# uTracker.net
KiCad netlist of a schematic drawn in EAGLE
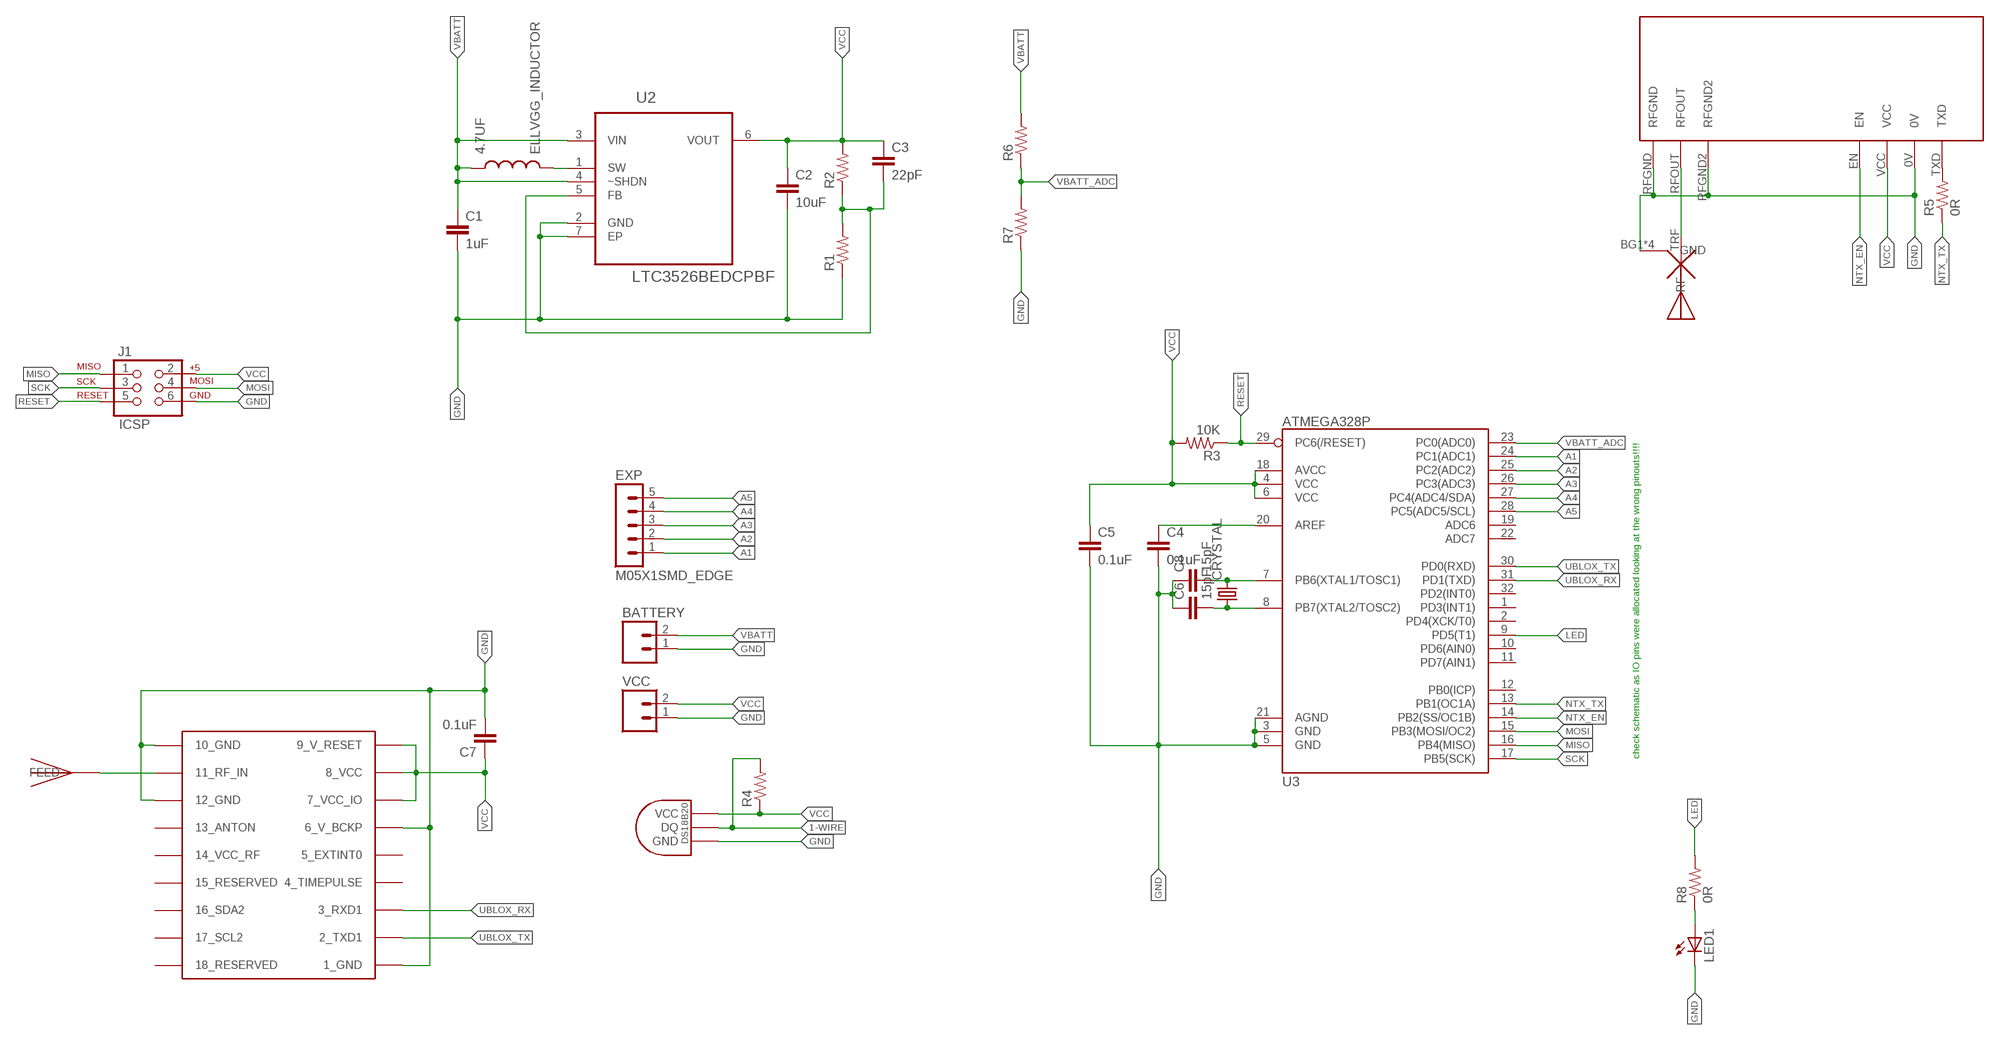
[diagram p0: schematic, sheet 1]

(export (version "E")
  (design (tool "Eeschema 10.0.6"))
  (components
    (comp (ref "4.7UF")
      (value "ELLVGG_INDUCTOR")
      (footprint "eagle-import:ELLVGG_INDUCTOR")
      (libsource (lib "eagle-import") (part "ELLVGG_INDUCTOR"))
    )
    (comp (ref "BATTERY")
      (value "M02PTH")
      (footprint "eagle-import:1X02")
      (libsource (lib "eagle-import") (part "M02PTH"))
    )
    (comp (ref "C1")
      (value "1uF")
      (footprint "eagle-import:0805")
      (libsource (lib "eagle-import") (part "CAP0805"))
    )
    (comp (ref "C2")
      (value "10uF")
      (footprint "eagle-import:0805")
      (libsource (lib "eagle-import") (part "CAP0805"))
    )
    (comp (ref "C3")
      (value "22pF")
      (footprint "eagle-import:0805")
      (libsource (lib "eagle-import") (part "CAP0805"))
    )
    (comp (ref "C4")
      (value "0.1uF")
      (footprint "eagle-import:0805")
      (libsource (lib "eagle-import") (part "CAP0805"))
    )
    (comp (ref "C5")
      (value "0.1uF")
      (footprint "eagle-import:0805")
      (libsource (lib "eagle-import") (part "CAP0805"))
    )
    (comp (ref "C6")
      (value "15pF")
      (footprint "eagle-import:0805")
      (libsource (lib "eagle-import") (part "CAP0805"))
    )
    (comp (ref "C7")
      (value "0.1uF")
      (footprint "eagle-import:0805")
      (libsource (lib "eagle-import") (part "CAP0805"))
    )
    (comp (ref "C8")
      (value "15pF")
      (footprint "eagle-import:0805")
      (libsource (lib "eagle-import") (part "CAP0805"))
    )
    (comp (ref "CRYSTAL")
      (value "ABRACON_ABM3_CRYSTALABM03_HC49")
      (footprint "eagle-import:ABM03_HC49")
      (libsource (lib "eagle-import") (part "ABRACON_ABM3_CRYSTALABM03_HC49"))
    )
    (comp (ref "EXP")
      (value "M05X1SMD_EDGE")
      (footprint "eagle-import:M05_SMD_EDGE")
      (libsource (lib "eagle-import") (part "M05X1SMD_EDGE"))
    )
    (comp (ref "J1")
      (value "ICSP")
      (footprint "eagle-import:ICSP_SMD_EDGE")
      (libsource (lib "eagle-import") (part "AVR_SPI_PRG_6SMD_EDGE"))
    )
    (comp (ref "LED1")
      (value "LED1206")
      (footprint "eagle-import:LED-1206")
      (libsource (lib "eagle-import") (part "LED1206"))
    )
    (comp (ref "R1")
      (value "RESISTOR0805-RES")
      (footprint "eagle-import:0805")
      (libsource (lib "eagle-import") (part "RESISTOR0805-RES"))
    )
    (comp (ref "R2")
      (value "RESISTOR0805-RES")
      (footprint "eagle-import:0805")
      (libsource (lib "eagle-import") (part "RESISTOR0805-RES"))
    )
    (comp (ref "R3")
      (value "10K")
      (footprint "eagle-import:0805")
      (libsource (lib "eagle-import") (part "RESISTOR0805-RES"))
    )
    (comp (ref "R4")
      (value "RESISTOR0805-RES")
      (footprint "eagle-import:0805")
      (libsource (lib "eagle-import") (part "RESISTOR0805-RES"))
    )
    (comp (ref "R5")
      (value "0R")
      (footprint "eagle-import:0805")
      (libsource (lib "eagle-import") (part "RESISTOR0805-RES"))
    )
    (comp (ref "R6")
      (value "RESISTOR0805-RES")
      (footprint "eagle-import:0805")
      (libsource (lib "eagle-import") (part "RESISTOR0805-RES"))
    )
    (comp (ref "R7")
      (value "RESISTOR0805-RES")
      (footprint "eagle-import:0805")
      (libsource (lib "eagle-import") (part "RESISTOR0805-RES"))
    )
    (comp (ref "R8")
      (value "0R")
      (footprint "eagle-import:0805")
      (libsource (lib "eagle-import") (part "RESISTOR0805-RES"))
    )
    (comp (ref "U$1")
      (value "ANTENNA")
      (footprint "eagle-import:ANTCONN_GNDPL")
      (libsource (lib "eagle-import") (part "ANTENNA"))
    )
    (comp (ref "U$2")
      (value "JTI_ANTENNA-1575AT43A40")
      (footprint "eagle-import:JTI_ANTENNA-1575AT43A40")
      (libsource (lib "eagle-import") (part "JTI_ANTENNA-1575AT43A40"))
    )
    (comp (ref "U$3")
      (value "NTX2")
      (footprint "eagle-import:NTX2")
      (libsource (lib "eagle-import") (part "NTX2"))
    )
    (comp (ref "U$4")
      (value "DS1820SOIC")
      (footprint "eagle-import:DS18B20_SOIC")
      (libsource (lib "eagle-import") (part "DS1820SOIC"))
    )
    (comp (ref "U2")
      (value "LTC3526BEDCPBF")
      (footprint "eagle-import:DFN200X200X80-7N")
      (fields (field (name "MPN") "LTC3526BEDC#PBF"))
      (libsource (lib "eagle-import") (part "LTC3526BEDCPBF"))
    )
    (comp (ref "U3")
      (value "ATMEGA328P")
      (footprint "eagle-import:TQFP32-08")
      (libsource (lib "eagle-import") (part "ATMEGA328_SMT"))
    )
    (comp (ref "UBLOX")
      (value "UBLOX_MAX-6")
      (footprint "eagle-import:UBLOX_MAX-6")
      (libsource (lib "eagle-import") (part "UBLOX_MAX-6"))
    )
    (comp (ref "VCC")
      (value "M02PTH")
      (footprint "eagle-import:1X02")
      (libsource (lib "eagle-import") (part "M02PTH"))
    )
  )
  (nets
    (net (code "1") (name "1-WIRE") (class "Default")
      (node (ref "R4") (pin "2") (pinfunction "2_2") (pintype "passive"))
      (node (ref "U$4") (pin "DQ") (pinfunction "DQ_DQ") (pintype "bidirectional"))
    )
    (net (code "2") (name "A1") (class "Default")
      (node (ref "EXP") (pin "1") (pinfunction "1_1") (pintype "passive"))
      (node (ref "U3") (pin "24") (pinfunction "PC1(ADC1)_24") (pintype "bidirectional"))
    )
    (net (code "3") (name "A2") (class "Default")
      (node (ref "EXP") (pin "2") (pinfunction "2_2") (pintype "passive"))
      (node (ref "U3") (pin "25") (pinfunction "PC2(ADC2)_25") (pintype "bidirectional"))
    )
    (net (code "4") (name "A3") (class "Default")
      (node (ref "EXP") (pin "3") (pinfunction "3_3") (pintype "passive"))
      (node (ref "U3") (pin "26") (pinfunction "PC3(ADC3)_26") (pintype "bidirectional"))
    )
    (net (code "5") (name "A4") (class "Default")
      (node (ref "EXP") (pin "4") (pinfunction "4_4") (pintype "passive"))
      (node (ref "U3") (pin "27") (pinfunction "PC4(ADC4/SDA)_27") (pintype "bidirectional"))
    )
    (net (code "6") (name "A5") (class "Default")
      (node (ref "EXP") (pin "5") (pinfunction "5_5") (pintype "passive"))
      (node (ref "U3") (pin "28") (pinfunction "PC5(ADC5/SCL)_28") (pintype "bidirectional"))
    )
    (net (code "7") (name "GND") (class "Default")
      (node (ref "BATTERY") (pin "1") (pinfunction "1_1") (pintype "passive"))
      (node (ref "C1") (pin "2") (pinfunction "2_2") (pintype "passive"))
      (node (ref "C2") (pin "2") (pinfunction "2_2") (pintype "passive"))
      (node (ref "C4") (pin "2") (pinfunction "2_2") (pintype "passive"))
      (node (ref "C5") (pin "2") (pinfunction "2_2") (pintype "passive"))
      (node (ref "C6") (pin "1") (pinfunction "1_1") (pintype "passive"))
      (node (ref "C7") (pin "2") (pinfunction "2_2") (pintype "passive"))
      (node (ref "C8") (pin "1") (pinfunction "1_1") (pintype "passive"))
      (node (ref "J1") (pin "6") (pinfunction "6_6") (pintype "passive"))
      (node (ref "LED1") (pin "C") (pinfunction "C_C") (pintype "passive"))
      (node (ref "R1") (pin "1") (pinfunction "1_1") (pintype "passive"))
      (node (ref "R7") (pin "1") (pinfunction "1_1") (pintype "passive"))
      (node (ref "U$1") (pin "BG1") (pinfunction "GND_BG1") (pintype "power_in"))
      (node (ref "U$1") (pin "BG2") (pinfunction "GND_BG2") (pintype "power_in"))
      (node (ref "U$1") (pin "TG1") (pinfunction "GND_TG1") (pintype "power_in"))
      (node (ref "U$1") (pin "TG2") (pinfunction "GND_TG2") (pintype "power_in"))
      (node (ref "U$3") (pin "0V") (pinfunction "0V_0V") (pintype "bidirectional"))
      (node (ref "U$3") (pin "RFGND") (pinfunction "RFGND_RFGND") (pintype "bidirectional"))
      (node (ref "U$3") (pin "RFGND2") (pinfunction "RFGND2_RFGND2") (pintype "bidirectional"))
      (node (ref "U$4") (pin "GND") (pinfunction "GND_GND") (pintype "power_in"))
      (node (ref "U2") (pin "2") (pinfunction "GND_2") (pintype "passive"))
      (node (ref "U2") (pin "7") (pinfunction "EP_7") (pintype "passive"))
      (node (ref "U3") (pin "21") (pinfunction "AGND_21") (pintype "bidirectional"))
      (node (ref "U3") (pin "3") (pinfunction "GND_3") (pintype "bidirectional"))
      (node (ref "U3") (pin "5") (pinfunction "GND_5") (pintype "bidirectional"))
      (node (ref "UBLOX") (pin "10_GND") (pinfunction "10_GND_10_GND") (pintype "power_in"))
      (node (ref "UBLOX") (pin "12_GND") (pinfunction "12_GND_12_GND") (pintype "power_in"))
      (node (ref "UBLOX") (pin "1_GND") (pinfunction "1_GND_1_GND") (pintype "power_in"))
      (node (ref "UBLOX") (pin "6_V_BCKP") (pinfunction "6_V_BCKP_6_V_BCKP") (pintype "bidirectional"))
      (node (ref "VCC") (pin "1") (pinfunction "1_1") (pintype "passive"))
    )
    (net (code "8") (name "LED") (class "Default")
      (node (ref "R8") (pin "2") (pinfunction "2_2") (pintype "passive"))
      (node (ref "U3") (pin "9") (pinfunction "PD5(T1)_9") (pintype "bidirectional"))
    )
    (net (code "9") (name "MISO") (class "Default")
      (node (ref "J1") (pin "1") (pinfunction "1_1") (pintype "passive"))
      (node (ref "U3") (pin "16") (pinfunction "PB4(MISO)_16") (pintype "bidirectional"))
    )
    (net (code "10") (name "MOSI") (class "Default")
      (node (ref "J1") (pin "4") (pinfunction "4_4") (pintype "passive"))
      (node (ref "U3") (pin "15") (pinfunction "PB3(MOSI/OC2)_15") (pintype "bidirectional"))
    )
    (net (code "11") (name "NTX_EN") (class "Default")
      (node (ref "U$3") (pin "EN") (pinfunction "EN_EN") (pintype "bidirectional"))
      (node (ref "U3") (pin "14") (pinfunction "PB2(SS/OC1B)_14") (pintype "bidirectional"))
    )
    (net (code "12") (name "NTX_TX") (class "Default")
      (node (ref "R5") (pin "1") (pinfunction "1_1") (pintype "passive"))
      (node (ref "U3") (pin "13") (pinfunction "PB1(OC1A)_13") (pintype "bidirectional"))
    )
    (net (code "13") (name "Net-(4.7UF-2)") (class "Default")
      (node (ref "4.7UF") (pin "P$2") (pinfunction "2_P$2") (pintype "passive"))
      (node (ref "U2") (pin "1") (pinfunction "SW_1") (pintype "passive"))
    )
    (net (code "14") (name "Net-(LED1-PadA)") (class "Default")
      (node (ref "LED1") (pin "A") (pinfunction "A_A") (pintype "passive"))
      (node (ref "R8") (pin "1") (pinfunction "1_1") (pintype "passive"))
    )
    (net (code "15") (name "Net-(R5-Pad2)") (class "Default")
      (node (ref "R5") (pin "2") (pinfunction "2_2") (pintype "passive"))
      (node (ref "U$3") (pin "TXD") (pinfunction "TXD_TXD") (pintype "bidirectional"))
    )
    (net (code "16") (name "Net-(U$1-RF)") (class "Default")
      (node (ref "U$1") (pin "TRF") (pinfunction "RF_TRF") (pintype "output"))
      (node (ref "U$3") (pin "RFOUT") (pinfunction "RFOUT_RFOUT") (pintype "bidirectional"))
    )
    (net (code "17") (name "Net-(U$2-PadFEED)") (class "Default")
      (node (ref "U$2") (pin "FEED") (pinfunction "FEED_FEED") (pintype "bidirectional"))
      (node (ref "UBLOX") (pin "11_RF_IN") (pinfunction "11_RF_IN_11_RF_IN") (pintype "bidirectional"))
    )
    (net (code "18") (name "Net-(U2-FB)") (class "Default")
      (node (ref "C3") (pin "2") (pinfunction "2_2") (pintype "passive"))
      (node (ref "R1") (pin "2") (pinfunction "2_2") (pintype "passive"))
      (node (ref "R2") (pin "1") (pinfunction "1_1") (pintype "passive"))
      (node (ref "U2") (pin "5") (pinfunction "FB_5") (pintype "input"))
    )
    (net (code "19") (name "Net-(U3-AREF)") (class "Default")
      (node (ref "C4") (pin "1") (pinfunction "1_1") (pintype "passive"))
      (node (ref "U3") (pin "20") (pinfunction "AREF_20") (pintype "bidirectional"))
    )
    (net (code "20") (name "Net-(U3-PB6(XTAL1{slash}TOSC1))") (class "Default")
      (node (ref "C8") (pin "2") (pinfunction "2_2") (pintype "passive"))
      (node (ref "CRYSTAL") (pin "2") (pinfunction "2_2") (pintype "passive"))
      (node (ref "U3") (pin "7") (pinfunction "PB6(XTAL1/TOSC1)_7") (pintype "bidirectional"))
    )
    (net (code "21") (name "Net-(U3-PB7(XTAL2{slash}TOSC2))") (class "Default")
      (node (ref "C6") (pin "2") (pinfunction "2_2") (pintype "passive"))
      (node (ref "CRYSTAL") (pin "1") (pinfunction "1_1") (pintype "passive"))
      (node (ref "U3") (pin "8") (pinfunction "PB7(XTAL2/TOSC2)_8") (pintype "bidirectional"))
    )
    (net (code "22") (name "RESET") (class "Default")
      (node (ref "J1") (pin "5") (pinfunction "5_5") (pintype "passive"))
      (node (ref "R3") (pin "1") (pinfunction "1_1") (pintype "passive"))
      (node (ref "U3") (pin "29") (pinfunction "PC6(/RESET)_29") (pintype "bidirectional"))
    )
    (net (code "23") (name "SCK") (class "Default")
      (node (ref "J1") (pin "3") (pinfunction "3_3") (pintype "passive"))
      (node (ref "U3") (pin "17") (pinfunction "PB5(SCK)_17") (pintype "bidirectional"))
    )
    (net (code "24") (name "UBLOX_RX") (class "Default")
      (node (ref "U3") (pin "31") (pinfunction "PD1(TXD)_31") (pintype "bidirectional"))
      (node (ref "UBLOX") (pin "3_RXD1") (pinfunction "3_RXD1_3_RXD1") (pintype "bidirectional"))
    )
    (net (code "25") (name "UBLOX_TX") (class "Default")
      (node (ref "U3") (pin "30") (pinfunction "PD0(RXD)_30") (pintype "bidirectional"))
      (node (ref "UBLOX") (pin "2_TXD1") (pinfunction "2_TXD1_2_TXD1") (pintype "bidirectional"))
    )
    (net (code "26") (name "VBATT") (class "Default")
      (node (ref "4.7UF") (pin "P$1") (pinfunction "1_P$1") (pintype "passive"))
      (node (ref "BATTERY") (pin "2") (pinfunction "2_2") (pintype "passive"))
      (node (ref "C1") (pin "1") (pinfunction "1_1") (pintype "passive"))
      (node (ref "R6") (pin "2") (pinfunction "2_2") (pintype "passive"))
      (node (ref "U2") (pin "3") (pinfunction "VIN_3") (pintype "power_in"))
      (node (ref "U2") (pin "4") (pinfunction "~{SHDN}_4") (pintype "input"))
    )
    (net (code "27") (name "VBATT_ADC") (class "Default")
      (node (ref "R6") (pin "1") (pinfunction "1_1") (pintype "passive"))
      (node (ref "R7") (pin "2") (pinfunction "2_2") (pintype "passive"))
      (node (ref "U3") (pin "23") (pinfunction "PC0(ADC0)_23") (pintype "bidirectional"))
    )
    (net (code "28") (name "VCC") (class "Default")
      (node (ref "C2") (pin "1") (pinfunction "1_1") (pintype "passive"))
      (node (ref "C3") (pin "1") (pinfunction "1_1") (pintype "passive"))
      (node (ref "C5") (pin "1") (pinfunction "1_1") (pintype "passive"))
      (node (ref "C7") (pin "1") (pinfunction "1_1") (pintype "passive"))
      (node (ref "J1") (pin "2") (pinfunction "2_2") (pintype "passive"))
      (node (ref "R2") (pin "2") (pinfunction "2_2") (pintype "passive"))
      (node (ref "R3") (pin "2") (pinfunction "2_2") (pintype "passive"))
      (node (ref "R4") (pin "1") (pinfunction "1_1") (pintype "passive"))
      (node (ref "U$3") (pin "VCC") (pinfunction "VCC_VCC") (pintype "bidirectional"))
      (node (ref "U$4") (pin "VCC") (pinfunction "VCC_VCC") (pintype "power_in"))
      (node (ref "U2") (pin "6") (pinfunction "VOUT_6") (pintype "output"))
      (node (ref "U3") (pin "18") (pinfunction "AVCC_18") (pintype "bidirectional"))
      (node (ref "U3") (pin "4") (pinfunction "VCC_4") (pintype "bidirectional"))
      (node (ref "U3") (pin "6") (pinfunction "VCC_6") (pintype "bidirectional"))
      (node (ref "UBLOX") (pin "7_VCC_IO") (pinfunction "7_VCC_IO_7_VCC_IO") (pintype "power_in"))
      (node (ref "UBLOX") (pin "8_VCC") (pinfunction "8_VCC_8_VCC") (pintype "power_in"))
      (node (ref "UBLOX") (pin "9_V_RESET") (pinfunction "9_V_RESET_9_V_RESET") (pintype "power_in"))
      (node (ref "VCC") (pin "2") (pinfunction "2_2") (pintype "passive"))
    )
    (net (code "29") (name "unconnected-(U3-ADC6-Pad19)") (class "Default")
      (node (ref "U3") (pin "19") (pinfunction "ADC6_19") (pintype "bidirectional"))
    )
    (net (code "30") (name "unconnected-(U3-ADC7-Pad22)") (class "Default")
      (node (ref "U3") (pin "22") (pinfunction "ADC7_22") (pintype "bidirectional"))
    )
    (net (code "31") (name "unconnected-(U3-PB0(ICP)-Pad12)") (class "Default")
      (node (ref "U3") (pin "12") (pinfunction "PB0(ICP)_12") (pintype "bidirectional"))
    )
    (net (code "32") (name "unconnected-(U3-PD2(INT0)-Pad32)") (class "Default")
      (node (ref "U3") (pin "32") (pinfunction "PD2(INT0)_32") (pintype "bidirectional"))
    )
    (net (code "33") (name "unconnected-(U3-PD3(INT1)-Pad1)") (class "Default")
      (node (ref "U3") (pin "1") (pinfunction "PD3(INT1)_1") (pintype "bidirectional"))
    )
    (net (code "34") (name "unconnected-(U3-PD4(XCK{slash}T0)-Pad2)") (class "Default")
      (node (ref "U3") (pin "2") (pinfunction "PD4(XCK/T0)_2") (pintype "bidirectional"))
    )
    (net (code "35") (name "unconnected-(U3-PD6(AIN0)-Pad10)") (class "Default")
      (node (ref "U3") (pin "10") (pinfunction "PD6(AIN0)_10") (pintype "bidirectional"))
    )
    (net (code "36") (name "unconnected-(U3-PD7(AIN1)-Pad11)") (class "Default")
      (node (ref "U3") (pin "11") (pinfunction "PD7(AIN1)_11") (pintype "bidirectional"))
    )
    (net (code "37") (name "unconnected-(UBLOX-Pad4_TIMEPULSE)") (class "Default")
      (node (ref "UBLOX") (pin "4_TIMEPULSE") (pinfunction "4_TIMEPULSE_4_TIMEPULSE") (pintype "bidirectional"))
    )
    (net (code "38") (name "unconnected-(UBLOX-Pad5_EXTINT0)") (class "Default")
      (node (ref "UBLOX") (pin "5_EXTINT0") (pinfunction "5_EXTINT0_5_EXTINT0") (pintype "bidirectional"))
    )
    (net (code "39") (name "unconnected-(UBLOX-Pad13_ANTON)") (class "Default")
      (node (ref "UBLOX") (pin "13_ANTON") (pinfunction "13_ANTON_13_ANTON") (pintype "bidirectional"))
    )
    (net (code "40") (name "unconnected-(UBLOX-Pad14_VCC_RF)") (class "Default")
      (node (ref "UBLOX") (pin "14_VCC_RF") (pinfunction "14_VCC_RF_14_VCC_RF") (pintype "bidirectional"))
    )
    (net (code "41") (name "unconnected-(UBLOX-Pad15_RESERVED)") (class "Default")
      (node (ref "UBLOX") (pin "15_RESERVED") (pinfunction "15_RESERVED_15_RESERVED") (pintype "bidirectional"))
    )
    (net (code "42") (name "unconnected-(UBLOX-Pad16_SDA2)") (class "Default")
      (node (ref "UBLOX") (pin "16_SDA2") (pinfunction "16_SDA2_16_SDA2") (pintype "bidirectional"))
    )
    (net (code "43") (name "unconnected-(UBLOX-Pad17_SCL2)") (class "Default")
      (node (ref "UBLOX") (pin "17_SCL2") (pinfunction "17_SCL2_17_SCL2") (pintype "bidirectional"))
    )
    (net (code "44") (name "unconnected-(UBLOX-Pad18_RESERVED)") (class "Default")
      (node (ref "UBLOX") (pin "18_RESERVED") (pinfunction "18_RESERVED_18_RESERVED") (pintype "bidirectional"))
    )
  )
)
